# HVD_Filtering.net
KiCad netlist of a schematic drawn in Altium Designer
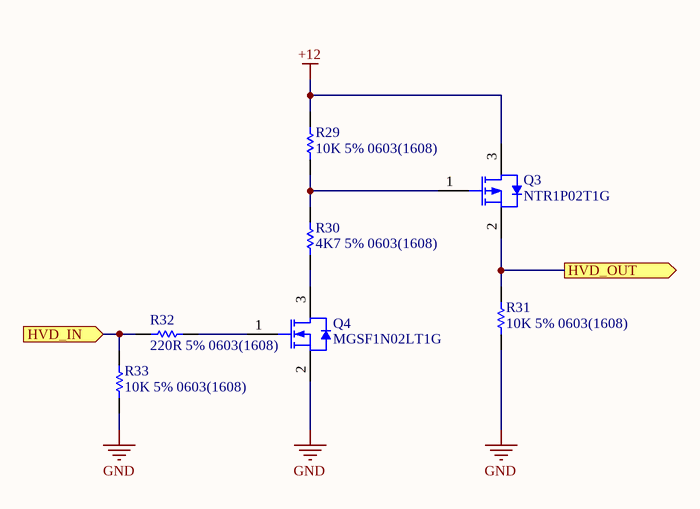
[diagram p0: HVD_Filtering.SchDoc]

(export (version "E")
  (design (tool "Eeschema 10.0.6"))
  (components
    (comp (ref "Q3")
      (value "NTR1P02T1G")
      (footprint "ONSC-SOT-23-3-318-08_V")
      (description "Power MOSFET, -20 V, -1 A, P-Channel, 3-Pin SOT-23, Pb-Free, Tape and Reel")
      (fields (field (name "MANUFACTURER") "On Semiconductor"))
      (libsource (lib "Altium Content Vault") (part "ONSC-PMOS-G1S2D3-3_D"))
    )
    (comp (ref "Q4")
      (value "MGSF1N02LT1G")
      (footprint "ONSC-SOT-23-3-318-08_V")
      (description "Power MOSFET, 750 mA, 20 V, N-Channel, 3-Pin SOT-23, Pb-Free, Tape and Reel")
      (fields (field (name "MANUFACTURER") "On Semiconductor"))
      (libsource (lib "Altium Content Vault") (part "ONSC-NMOS-G1S2D3-3"))
    )
    (comp (ref "R29")
      (value "10K 5% 0603(1608)")
      (footprint "RESC0603(1608)_N")
      (description "10K 0.1W 5% 0603 (1608 Metric)  SMD")
      (fields (field (name "TOLERANCE") "5 %") (field (name "POWER") "0.1 W"))
      (libsource (lib "Altium Content Vault") (part "RES"))
    )
    (comp (ref "R30")
      (value "4K7 5% 0603(1608)")
      (footprint "RESC0603(1608)_N")
      (description "4K7 0.1W 5% 0603 (1608 Metric)  SMD")
      (fields (field (name "TOLERANCE") "5 %") (field (name "POWER") "0.1 W"))
      (libsource (lib "Altium Content Vault") (part "RES"))
    )
    (comp (ref "R31")
      (value "10K 5% 0603(1608)")
      (footprint "RESC0603(1608)_N")
      (description "10K 0.1W 5% 0603 (1608 Metric)  SMD")
      (fields (field (name "TOLERANCE") "5 %") (field (name "POWER") "0.1 W"))
      (libsource (lib "Altium Content Vault") (part "RES"))
    )
    (comp (ref "R32")
      (value "220R 5% 0603(1608)")
      (footprint "RESC0603(1608)_M")
      (description "220R 0.1W 5% 0603 (1608 Metric)  SMD")
      (fields (field (name "POWER") "0.1 W") (field (name "TOLERANCE") "5 %"))
      (libsource (lib "Altium Content Vault") (part "RES"))
    )
    (comp (ref "R33")
      (value "10K 5% 0603(1608)")
      (footprint "RESC0603(1608)_N")
      (description "10K 0.1W 5% 0603 (1608 Metric)  SMD")
      (fields (field (name "TOLERANCE") "5 %") (field (name "POWER") "0.1 W"))
      (libsource (lib "Altium Content Vault") (part "RES"))
    )
  )
  (nets
    (net (code "1") (name "+12") (class "Default")
      (node (ref "Q3") (pin "3") (pinfunction "D_3") (pintype "passive"))
      (node (ref "R29") (pin "2") (pinfunction "2_2") (pintype "passive"))
    )
    (net (code "2") (name "/HVD_IN") (class "Default")
      (node (ref "R32") (pin "1") (pinfunction "1_1") (pintype "passive"))
      (node (ref "R33") (pin "2") (pinfunction "2_2") (pintype "passive"))
    )
    (net (code "3") (name "/HVD_OUT") (class "Default")
      (node (ref "Q3") (pin "2") (pinfunction "S_2") (pintype "passive"))
      (node (ref "R31") (pin "2") (pinfunction "2_2") (pintype "passive"))
    )
    (net (code "4") (name "GND") (class "Default")
      (node (ref "Q4") (pin "2") (pinfunction "S_2") (pintype "passive"))
      (node (ref "R31") (pin "1") (pinfunction "1_1") (pintype "passive"))
      (node (ref "R33") (pin "1") (pinfunction "1_1") (pintype "passive"))
    )
    (net (code "5") (name "Net-(Q3-G)") (class "Default")
      (node (ref "Q3") (pin "1") (pinfunction "G_1") (pintype "passive"))
      (node (ref "R29") (pin "1") (pinfunction "1_1") (pintype "passive"))
      (node (ref "R30") (pin "2") (pinfunction "2_2") (pintype "passive"))
    )
    (net (code "6") (name "Net-(Q4-D)") (class "Default")
      (node (ref "Q4") (pin "3") (pinfunction "D_3") (pintype "passive"))
      (node (ref "R30") (pin "1") (pinfunction "1_1") (pintype "passive"))
    )
    (net (code "7") (name "Net-(Q4-G)") (class "Default")
      (node (ref "Q4") (pin "1") (pinfunction "G_1") (pintype "passive"))
      (node (ref "R32") (pin "2") (pinfunction "2_2") (pintype "passive"))
    )
  )
)
